# Logging_board.net
KiCad netlist of a schematic drawn in EAGLE
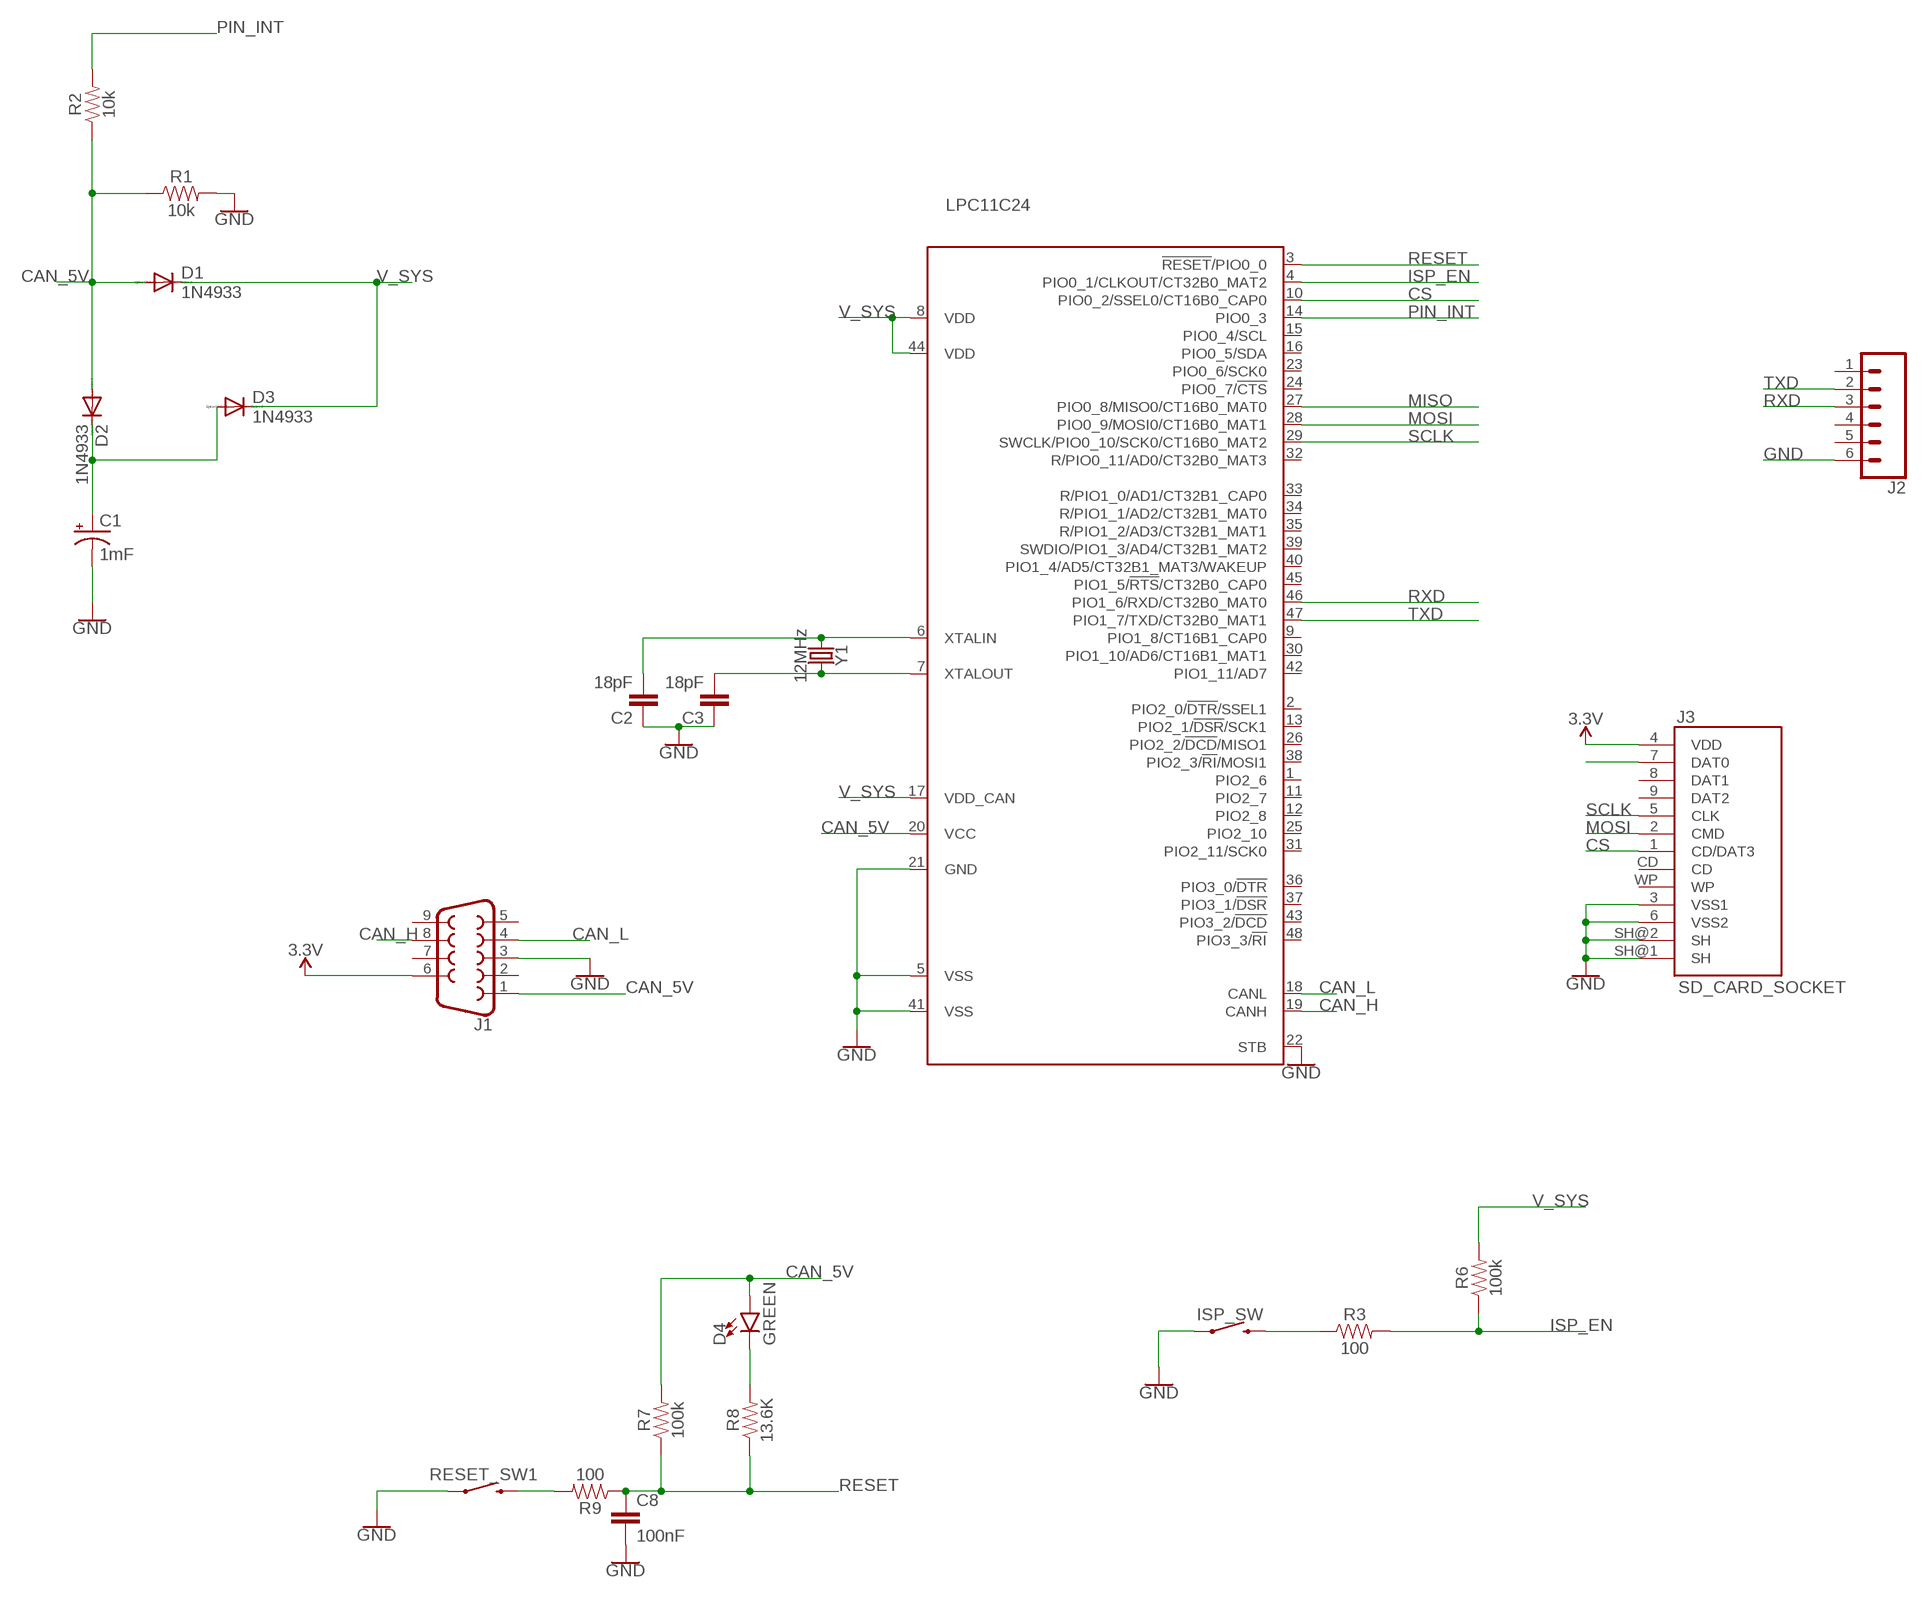
[diagram p0: schematic, sheet 1]

(export (version "E")
  (design (tool "Eeschema 10.0.6"))
  (components
    (comp (ref "C1")
      (value "1mF")
      (footprint "eagle-import:CPOL-RADIAL-5MM-10MM")
      (libsource (lib "eagle-import") (part "1000UF-RADIAL-5MM-25V-20%"))
    )
    (comp (ref "C2")
      (value "18pF")
      (footprint "eagle-import:CAP-PTH-2.54")
      (libsource (lib "eagle-import") (part "22PF-PTH-2.54MM-200V-5%"))
    )
    (comp (ref "C3")
      (value "18pF")
      (footprint "eagle-import:CAP-PTH-2.54")
      (libsource (lib "eagle-import") (part "22PF-PTH-2.54MM-200V-5%"))
    )
    (comp (ref "C8")
      (value "100nF")
      (footprint "eagle-import:CAP-PTH-2.54")
      (libsource (lib "eagle-import") (part "22PF-PTH-2.54MM-200V-5%"))
    )
    (comp (ref "D1")
      (value "1N4933")
      (footprint "eagle-import:DO41-10")
      (libsource (lib "eagle-import") (part "1N4933"))
    )
    (comp (ref "D2")
      (value "1N4933")
      (footprint "eagle-import:DO41-10")
      (libsource (lib "eagle-import") (part "1N4933"))
    )
    (comp (ref "D3")
      (value "1N4933")
      (footprint "eagle-import:DO41-10")
      (libsource (lib "eagle-import") (part "1N4933"))
    )
    (comp (ref "D4")
      (value "GREEN")
      (footprint "eagle-import:LED-1206")
      (libsource (lib "eagle-import") (part "LED-GREEN1206"))
    )
    (comp (ref "ISP_SW")
      (value "MOMENTARY-SWITCH-SPST-PTH-6.0MM")
      (footprint "eagle-import:TACTILE_SWITCH_PTH_6.0MM")
      (libsource (lib "eagle-import") (part "MOMENTARY-SWITCH-SPST-PTH-6.0MM"))
    )
    (comp (ref "J1")
      (value "DB9FEMALE")
      (footprint "eagle-import:DB9")
      (libsource (lib "eagle-import") (part "DB9FEMALE"))
    )
    (comp (ref "J2")
      (value "CONN_06SILK_FEMALE_PTH")
      (footprint "eagle-import:1X06")
      (libsource (lib "eagle-import") (part "CONN_06SILK_FEMALE_PTH"))
    )
    (comp (ref "J3")
      (value "SD_CARD_SOCKET")
      (footprint "eagle-import:SD")
      (libsource (lib "eagle-import") (part "SD_CARD_SOCKET"))
    )
    (comp (ref "LPC11C24")
      (value "LPC11C22/24-LQFP48")
      (footprint "eagle-import:LQFP48")
      (libsource (lib "eagle-import") (part "LPC11C22/24-LQFP48"))
    )
    (comp (ref "R1")
      (value "10k")
      (footprint "eagle-import:AXIAL-0.3")
      (libsource (lib "eagle-import") (part "10KOHM-HORIZ-1/4W-1%"))
    )
    (comp (ref "R2")
      (value "10k")
      (footprint "eagle-import:AXIAL-0.3")
      (libsource (lib "eagle-import") (part "10KOHM-HORIZ-1/4W-1%"))
    )
    (comp (ref "R3")
      (value "100")
      (footprint "eagle-import:AXIAL-0.3")
      (libsource (lib "eagle-import") (part "100OHM-HORIZ-1/4W-1%"))
    )
    (comp (ref "R6")
      (value "100k")
      (footprint "eagle-import:AXIAL-0.3")
      (libsource (lib "eagle-import") (part "100KOHM-HORIZ-1/4W-1%"))
    )
    (comp (ref "R7")
      (value "100k")
      (footprint "eagle-import:AXIAL-0.3")
      (libsource (lib "eagle-import") (part "100KOHM-HORIZ-1/4W-1%"))
    )
    (comp (ref "R8")
      (value "13.6K")
      (footprint "eagle-import:AXIAL-0.3")
      (libsource (lib "eagle-import") (part "100KOHM-HORIZ-1/4W-1%"))
    )
    (comp (ref "R9")
      (value "100")
      (footprint "eagle-import:AXIAL-0.3")
      (libsource (lib "eagle-import") (part "100KOHM-HORIZ-1/4W-1%"))
    )
    (comp (ref "RESET_SW1")
      (value "MOMENTARY-SWITCH-SPST-PTH-6.0MM")
      (footprint "eagle-import:TACTILE_SWITCH_PTH_6.0MM")
      (libsource (lib "eagle-import") (part "MOMENTARY-SWITCH-SPST-PTH-6.0MM"))
    )
    (comp (ref "Y1")
      (value "12MHz")
      (footprint "eagle-import:HC49US")
      (libsource (lib "eagle-import") (part "CRYSTAL-16MHZPTH-HC49US"))
    )
  )
  (nets
    (net (code "1") (name "/CAN_5V") (class "Default")
      (node (ref "D1") (pin "A") (pinfunction "A_A") (pintype "passive"))
      (node (ref "D2") (pin "A") (pinfunction "A_A") (pintype "passive"))
      (node (ref "D4") (pin "A") (pinfunction "A_A") (pintype "passive"))
      (node (ref "J1") (pin "1") (pinfunction "1_1") (pintype "passive"))
      (node (ref "LPC11C24") (pin "20") (pinfunction "VCC_20") (pintype "power_in"))
      (node (ref "R1") (pin "P$1") (pinfunction "1_P$1") (pintype "passive"))
      (node (ref "R2") (pin "P$1") (pinfunction "1_P$1") (pintype "passive"))
      (node (ref "R7") (pin "P$2") (pinfunction "2_P$2") (pintype "passive"))
    )
    (net (code "2") (name "/CAN_H") (class "Default")
      (node (ref "J1") (pin "8") (pinfunction "8_8") (pintype "passive"))
      (node (ref "LPC11C24") (pin "19") (pinfunction "CANH_19") (pintype "bidirectional"))
    )
    (net (code "3") (name "/CAN_L") (class "Default")
      (node (ref "J1") (pin "4") (pinfunction "4_4") (pintype "passive"))
      (node (ref "LPC11C24") (pin "18") (pinfunction "CANL_18") (pintype "bidirectional"))
    )
    (net (code "4") (name "/CS") (class "Default")
      (node (ref "J3") (pin "1") (pinfunction "CD/DAT3_1") (pintype "bidirectional"))
      (node (ref "LPC11C24") (pin "10") (pinfunction "PIO0_2/SSEL0/CT16B0_CAP0_10") (pintype "bidirectional"))
    )
    (net (code "5") (name "/ISP_EN") (class "Default")
      (node (ref "LPC11C24") (pin "4") (pinfunction "PIO0_1/CLKOUT/CT32B0_MAT2_4") (pintype "bidirectional"))
      (node (ref "R3") (pin "P$2") (pinfunction "2_P$2") (pintype "passive"))
      (node (ref "R6") (pin "P$1") (pinfunction "1_P$1") (pintype "passive"))
    )
    (net (code "6") (name "/MISO") (class "Default")
      (node (ref "LPC11C24") (pin "27") (pinfunction "PIO0_8/MISO0/CT16B0_MAT0_27") (pintype "bidirectional"))
    )
    (net (code "7") (name "/MOSI") (class "Default")
      (node (ref "J3") (pin "2") (pinfunction "CMD_2") (pintype "bidirectional"))
      (node (ref "LPC11C24") (pin "28") (pinfunction "PIO0_9/MOSI0/CT16B0_MAT1_28") (pintype "bidirectional"))
    )
    (net (code "8") (name "/PIN_INT") (class "Default")
      (node (ref "LPC11C24") (pin "14") (pinfunction "PIO0_3_14") (pintype "bidirectional"))
      (node (ref "R2") (pin "P$2") (pinfunction "2_P$2") (pintype "passive"))
    )
    (net (code "9") (name "/RESET") (class "Default")
      (node (ref "C8") (pin "1") (pinfunction "1_1") (pintype "passive"))
      (node (ref "LPC11C24") (pin "3") (pinfunction "~{RESET}/PIO0_0_3") (pintype "bidirectional"))
      (node (ref "R7") (pin "P$1") (pinfunction "1_P$1") (pintype "passive"))
      (node (ref "R8") (pin "P$1") (pinfunction "1_P$1") (pintype "passive"))
      (node (ref "R9") (pin "P$1") (pinfunction "1_P$1") (pintype "passive"))
    )
    (net (code "10") (name "/RXD") (class "Default")
      (node (ref "J2") (pin "3") (pinfunction "3_3") (pintype "passive"))
      (node (ref "LPC11C24") (pin "46") (pinfunction "PIO1_6/RXD/CT32B0_MAT0_46") (pintype "bidirectional"))
    )
    (net (code "11") (name "/SCLK") (class "Default")
      (node (ref "J3") (pin "5") (pinfunction "CLK_5") (pintype "bidirectional"))
      (node (ref "LPC11C24") (pin "29") (pinfunction "SWCLK/PIO0_10/SCK0/CT16B0_MAT2_29") (pintype "bidirectional"))
    )
    (net (code "12") (name "/TXD") (class "Default")
      (node (ref "J2") (pin "2") (pinfunction "2_2") (pintype "passive"))
      (node (ref "LPC11C24") (pin "47") (pinfunction "PIO1_7/TXD/CT32B0_MAT1_47") (pintype "bidirectional"))
    )
    (net (code "13") (name "/V_SYS") (class "Default")
      (node (ref "D1") (pin "C") (pinfunction "C_C") (pintype "passive"))
      (node (ref "D3") (pin "C") (pinfunction "C_C") (pintype "passive"))
      (node (ref "LPC11C24") (pin "17") (pinfunction "VDD_CAN_17") (pintype "power_in"))
      (node (ref "LPC11C24") (pin "44") (pinfunction "VDD_44") (pintype "power_in"))
      (node (ref "LPC11C24") (pin "8") (pinfunction "VDD_8") (pintype "power_in"))
      (node (ref "R6") (pin "P$2") (pinfunction "2_P$2") (pintype "passive"))
    )
    (net (code "14") (name "3.3V") (class "Default")
      (node (ref "J1") (pin "6") (pinfunction "6_6") (pintype "passive"))
      (node (ref "J3") (pin "4") (pinfunction "VDD_4") (pintype "power_in"))
    )
    (net (code "15") (name "GND") (class "Default")
      (node (ref "C1") (pin "-") (pinfunction "-_-") (pintype "passive"))
      (node (ref "C2") (pin "1") (pinfunction "1_1") (pintype "passive"))
      (node (ref "C3") (pin "1") (pinfunction "1_1") (pintype "passive"))
      (node (ref "C8") (pin "2") (pinfunction "2_2") (pintype "passive"))
      (node (ref "ISP_SW") (pin "1") (pinfunction "1_1") (pintype "passive"))
      (node (ref "J1") (pin "3") (pinfunction "3_3") (pintype "passive"))
      (node (ref "J2") (pin "6") (pinfunction "6_6") (pintype "passive"))
      (node (ref "J3") (pin "3") (pinfunction "VSS1_3") (pintype "power_in"))
      (node (ref "J3") (pin "6") (pinfunction "VSS2_6") (pintype "power_in"))
      (node (ref "J3") (pin "SH@1") (pinfunction "SH_SH@1") (pintype "bidirectional"))
      (node (ref "J3") (pin "SH@2") (pinfunction "SH_SH@2") (pintype "bidirectional"))
      (node (ref "LPC11C24") (pin "21") (pinfunction "GND_21") (pintype "power_in"))
      (node (ref "LPC11C24") (pin "22") (pinfunction "STB_22") (pintype "bidirectional"))
      (node (ref "LPC11C24") (pin "41") (pinfunction "VSS_41") (pintype "power_in"))
      (node (ref "LPC11C24") (pin "5") (pinfunction "VSS_5") (pintype "power_in"))
      (node (ref "R1") (pin "P$2") (pinfunction "2_P$2") (pintype "passive"))
      (node (ref "RESET_SW1") (pin "1") (pinfunction "1_1") (pintype "passive"))
    )
    (net (code "16") (name "Net-(C1-Pad+)") (class "Default")
      (node (ref "C1") (pin "+") (pinfunction "+_+") (pintype "passive"))
      (node (ref "D2") (pin "C") (pinfunction "C_C") (pintype "passive"))
      (node (ref "D3") (pin "A") (pinfunction "A_A") (pintype "passive"))
    )
    (net (code "17") (name "Net-(ISP_SW-2)") (class "Default")
      (node (ref "ISP_SW") (pin "3") (pinfunction "2_3") (pintype "passive"))
      (node (ref "R3") (pin "P$1") (pinfunction "1_P$1") (pintype "passive"))
    )
    (net (code "18") (name "Net-(LPC11C24-XTALIN)") (class "Default")
      (node (ref "C2") (pin "2") (pinfunction "2_2") (pintype "passive"))
      (node (ref "LPC11C24") (pin "6") (pinfunction "XTALIN_6") (pintype "passive"))
      (node (ref "Y1") (pin "1") (pinfunction "1_1") (pintype "passive"))
    )
    (net (code "19") (name "Net-(LPC11C24-XTALOUT)") (class "Default")
      (node (ref "C3") (pin "2") (pinfunction "2_2") (pintype "passive"))
      (node (ref "LPC11C24") (pin "7") (pinfunction "XTALOUT_7") (pintype "passive"))
      (node (ref "Y1") (pin "2") (pinfunction "2_2") (pintype "passive"))
    )
    (net (code "20") (name "Net-(R8-2)") (class "Default")
      (node (ref "D4") (pin "C") (pinfunction "C_C") (pintype "passive"))
      (node (ref "R8") (pin "P$2") (pinfunction "2_P$2") (pintype "passive"))
    )
    (net (code "21") (name "Net-(R9-2)") (class "Default")
      (node (ref "R9") (pin "P$2") (pinfunction "2_P$2") (pintype "passive"))
      (node (ref "RESET_SW1") (pin "3") (pinfunction "2_3") (pintype "passive"))
    )
    (net (code "22") (name "unconnected-(J1-Pad2)") (class "Default")
      (node (ref "J1") (pin "2") (pinfunction "2_2") (pintype "passive"))
    )
    (net (code "23") (name "unconnected-(J1-Pad5)") (class "Default")
      (node (ref "J1") (pin "5") (pinfunction "5_5") (pintype "passive"))
    )
    (net (code "24") (name "unconnected-(J1-Pad7)") (class "Default")
      (node (ref "J1") (pin "7") (pinfunction "7_7") (pintype "passive"))
    )
    (net (code "25") (name "unconnected-(J1-Pad9)") (class "Default")
      (node (ref "J1") (pin "9") (pinfunction "9_9") (pintype "passive"))
    )
    (net (code "26") (name "unconnected-(J2-Pad1)") (class "Default")
      (node (ref "J2") (pin "1") (pinfunction "1_1") (pintype "passive"))
    )
    (net (code "27") (name "unconnected-(J2-Pad4)") (class "Default")
      (node (ref "J2") (pin "4") (pinfunction "4_4") (pintype "passive"))
    )
    (net (code "28") (name "unconnected-(J2-Pad5)") (class "Default")
      (node (ref "J2") (pin "5") (pinfunction "5_5") (pintype "passive"))
    )
    (net (code "29") (name "unconnected-(J3-DAT0-Pad7)") (class "Default")
      (node (ref "J3") (pin "7") (pinfunction "DAT0_7") (pintype "bidirectional"))
    )
    (net (code "30") (name "unconnected-(J3-DAT1-Pad8)") (class "Default")
      (node (ref "J3") (pin "8") (pinfunction "DAT1_8") (pintype "bidirectional"))
    )
    (net (code "31") (name "unconnected-(J3-DAT2-Pad9)") (class "Default")
      (node (ref "J3") (pin "9") (pinfunction "DAT2_9") (pintype "bidirectional"))
    )
    (net (code "32") (name "unconnected-(J3-PadCD)") (class "Default")
      (node (ref "J3") (pin "CD") (pinfunction "CD_CD") (pintype "bidirectional"))
    )
    (net (code "33") (name "unconnected-(J3-PadWP)") (class "Default")
      (node (ref "J3") (pin "WP") (pinfunction "WP_WP") (pintype "bidirectional"))
    )
    (net (code "34") (name "unconnected-(LPC11C24-PIO0_4{slash}SCL-Pad15)") (class "Default")
      (node (ref "LPC11C24") (pin "15") (pinfunction "PIO0_4/SCL_15") (pintype "bidirectional"))
    )
    (net (code "35") (name "unconnected-(LPC11C24-PIO0_5{slash}SDA-Pad16)") (class "Default")
      (node (ref "LPC11C24") (pin "16") (pinfunction "PIO0_5/SDA_16") (pintype "bidirectional"))
    )
    (net (code "36") (name "unconnected-(LPC11C24-PIO0_6{slash}SCK0-Pad23)") (class "Default")
      (node (ref "LPC11C24") (pin "23") (pinfunction "PIO0_6/SCK0_23") (pintype "bidirectional"))
    )
    (net (code "37") (name "unconnected-(LPC11C24-PIO0_7{slash}~{CTS}-Pad24)") (class "Default")
      (node (ref "LPC11C24") (pin "24") (pinfunction "PIO0_7/~{CTS}_24") (pintype "bidirectional"))
    )
    (net (code "38") (name "unconnected-(LPC11C24-PIO1_4{slash}AD5{slash}CT32B1_MAT3{slash}WAKEUP-Pad40)") (class "Default")
      (node (ref "LPC11C24") (pin "40") (pinfunction "PIO1_4/AD5/CT32B1_MAT3/WAKEUP_40") (pintype "bidirectional"))
    )
    (net (code "39") (name "unconnected-(LPC11C24-PIO1_5{slash}~{RTS}{slash}CT32B0_CAP0-Pad45)") (class "Default")
      (node (ref "LPC11C24") (pin "45") (pinfunction "PIO1_5/~{RTS}/CT32B0_CAP0_45") (pintype "bidirectional"))
    )
    (net (code "40") (name "unconnected-(LPC11C24-PIO1_8{slash}CT16B1_CAP0-Pad9)") (class "Default")
      (node (ref "LPC11C24") (pin "9") (pinfunction "PIO1_8/CT16B1_CAP0_9") (pintype "bidirectional"))
    )
    (net (code "41") (name "unconnected-(LPC11C24-PIO1_10{slash}AD6{slash}CT16B1_MAT1-Pad30)") (class "Default")
      (node (ref "LPC11C24") (pin "30") (pinfunction "PIO1_10/AD6/CT16B1_MAT1_30") (pintype "bidirectional"))
    )
    (net (code "42") (name "unconnected-(LPC11C24-PIO1_11{slash}AD7-Pad42)") (class "Default")
      (node (ref "LPC11C24") (pin "42") (pinfunction "PIO1_11/AD7_42") (pintype "bidirectional"))
    )
    (net (code "43") (name "unconnected-(LPC11C24-PIO2_0{slash}~{DTR}{slash}SSEL1-Pad2)") (class "Default")
      (node (ref "LPC11C24") (pin "2") (pinfunction "PIO2_0/~{DTR}/SSEL1_2") (pintype "bidirectional"))
    )
    (net (code "44") (name "unconnected-(LPC11C24-PIO2_1{slash}~{DSR}{slash}SCK1-Pad13)") (class "Default")
      (node (ref "LPC11C24") (pin "13") (pinfunction "PIO2_1/~{DSR}/SCK1_13") (pintype "bidirectional"))
    )
    (net (code "45") (name "unconnected-(LPC11C24-PIO2_2{slash}~{DCD}{slash}MISO1-Pad26)") (class "Default")
      (node (ref "LPC11C24") (pin "26") (pinfunction "PIO2_2/~{DCD}/MISO1_26") (pintype "bidirectional"))
    )
    (net (code "46") (name "unconnected-(LPC11C24-PIO2_3{slash}~{RI}{slash}MOSI1-Pad38)") (class "Default")
      (node (ref "LPC11C24") (pin "38") (pinfunction "PIO2_3/~{RI}/MOSI1_38") (pintype "bidirectional"))
    )
    (net (code "47") (name "unconnected-(LPC11C24-PIO2_6-Pad1)") (class "Default")
      (node (ref "LPC11C24") (pin "1") (pinfunction "PIO2_6_1") (pintype "bidirectional"))
    )
    (net (code "48") (name "unconnected-(LPC11C24-PIO2_7-Pad11)") (class "Default")
      (node (ref "LPC11C24") (pin "11") (pinfunction "PIO2_7_11") (pintype "bidirectional"))
    )
    (net (code "49") (name "unconnected-(LPC11C24-PIO2_8-Pad12)") (class "Default")
      (node (ref "LPC11C24") (pin "12") (pinfunction "PIO2_8_12") (pintype "bidirectional"))
    )
    (net (code "50") (name "unconnected-(LPC11C24-PIO2_10-Pad25)") (class "Default")
      (node (ref "LPC11C24") (pin "25") (pinfunction "PIO2_10_25") (pintype "bidirectional"))
    )
    (net (code "51") (name "unconnected-(LPC11C24-PIO2_11{slash}SCK0-Pad31)") (class "Default")
      (node (ref "LPC11C24") (pin "31") (pinfunction "PIO2_11/SCK0_31") (pintype "bidirectional"))
    )
    (net (code "52") (name "unconnected-(LPC11C24-PIO3_0{slash}~{DTR}-Pad36)") (class "Default")
      (node (ref "LPC11C24") (pin "36") (pinfunction "PIO3_0/~{DTR}_36") (pintype "bidirectional"))
    )
    (net (code "53") (name "unconnected-(LPC11C24-PIO3_1{slash}~{DSR}-Pad37)") (class "Default")
      (node (ref "LPC11C24") (pin "37") (pinfunction "PIO3_1/~{DSR}_37") (pintype "bidirectional"))
    )
    (net (code "54") (name "unconnected-(LPC11C24-PIO3_2{slash}~{DCD}-Pad43)") (class "Default")
      (node (ref "LPC11C24") (pin "43") (pinfunction "PIO3_2/~{DCD}_43") (pintype "bidirectional"))
    )
    (net (code "55") (name "unconnected-(LPC11C24-PIO3_3{slash}~{RI}-Pad48)") (class "Default")
      (node (ref "LPC11C24") (pin "48") (pinfunction "PIO3_3/~{RI}_48") (pintype "bidirectional"))
    )
    (net (code "56") (name "unconnected-(LPC11C24-R{slash}PIO0_11{slash}AD0{slash}CT32B0_MAT3-Pad32)") (class "Default")
      (node (ref "LPC11C24") (pin "32") (pinfunction "R/PIO0_11/AD0/CT32B0_MAT3_32") (pintype "bidirectional"))
    )
    (net (code "57") (name "unconnected-(LPC11C24-R{slash}PIO1_0{slash}AD1{slash}CT32B1_CAP0-Pad33)") (class "Default")
      (node (ref "LPC11C24") (pin "33") (pinfunction "R/PIO1_0/AD1/CT32B1_CAP0_33") (pintype "bidirectional"))
    )
    (net (code "58") (name "unconnected-(LPC11C24-R{slash}PIO1_1{slash}AD2{slash}CT32B1_MAT0-Pad34)") (class "Default")
      (node (ref "LPC11C24") (pin "34") (pinfunction "R/PIO1_1/AD2/CT32B1_MAT0_34") (pintype "bidirectional"))
    )
    (net (code "59") (name "unconnected-(LPC11C24-R{slash}PIO1_2{slash}AD3{slash}CT32B1_MAT1-Pad35)") (class "Default")
      (node (ref "LPC11C24") (pin "35") (pinfunction "R/PIO1_2/AD3/CT32B1_MAT1_35") (pintype "bidirectional"))
    )
    (net (code "60") (name "unconnected-(LPC11C24-SWDIO{slash}PIO1_3{slash}AD4{slash}CT32B1_MAT2-Pad39)") (class "Default")
      (node (ref "LPC11C24") (pin "39") (pinfunction "SWDIO/PIO1_3/AD4/CT32B1_MAT2_39") (pintype "bidirectional"))
    )
  )
)
